# 3xCV.net
KiCad netlist of a schematic drawn in EAGLE
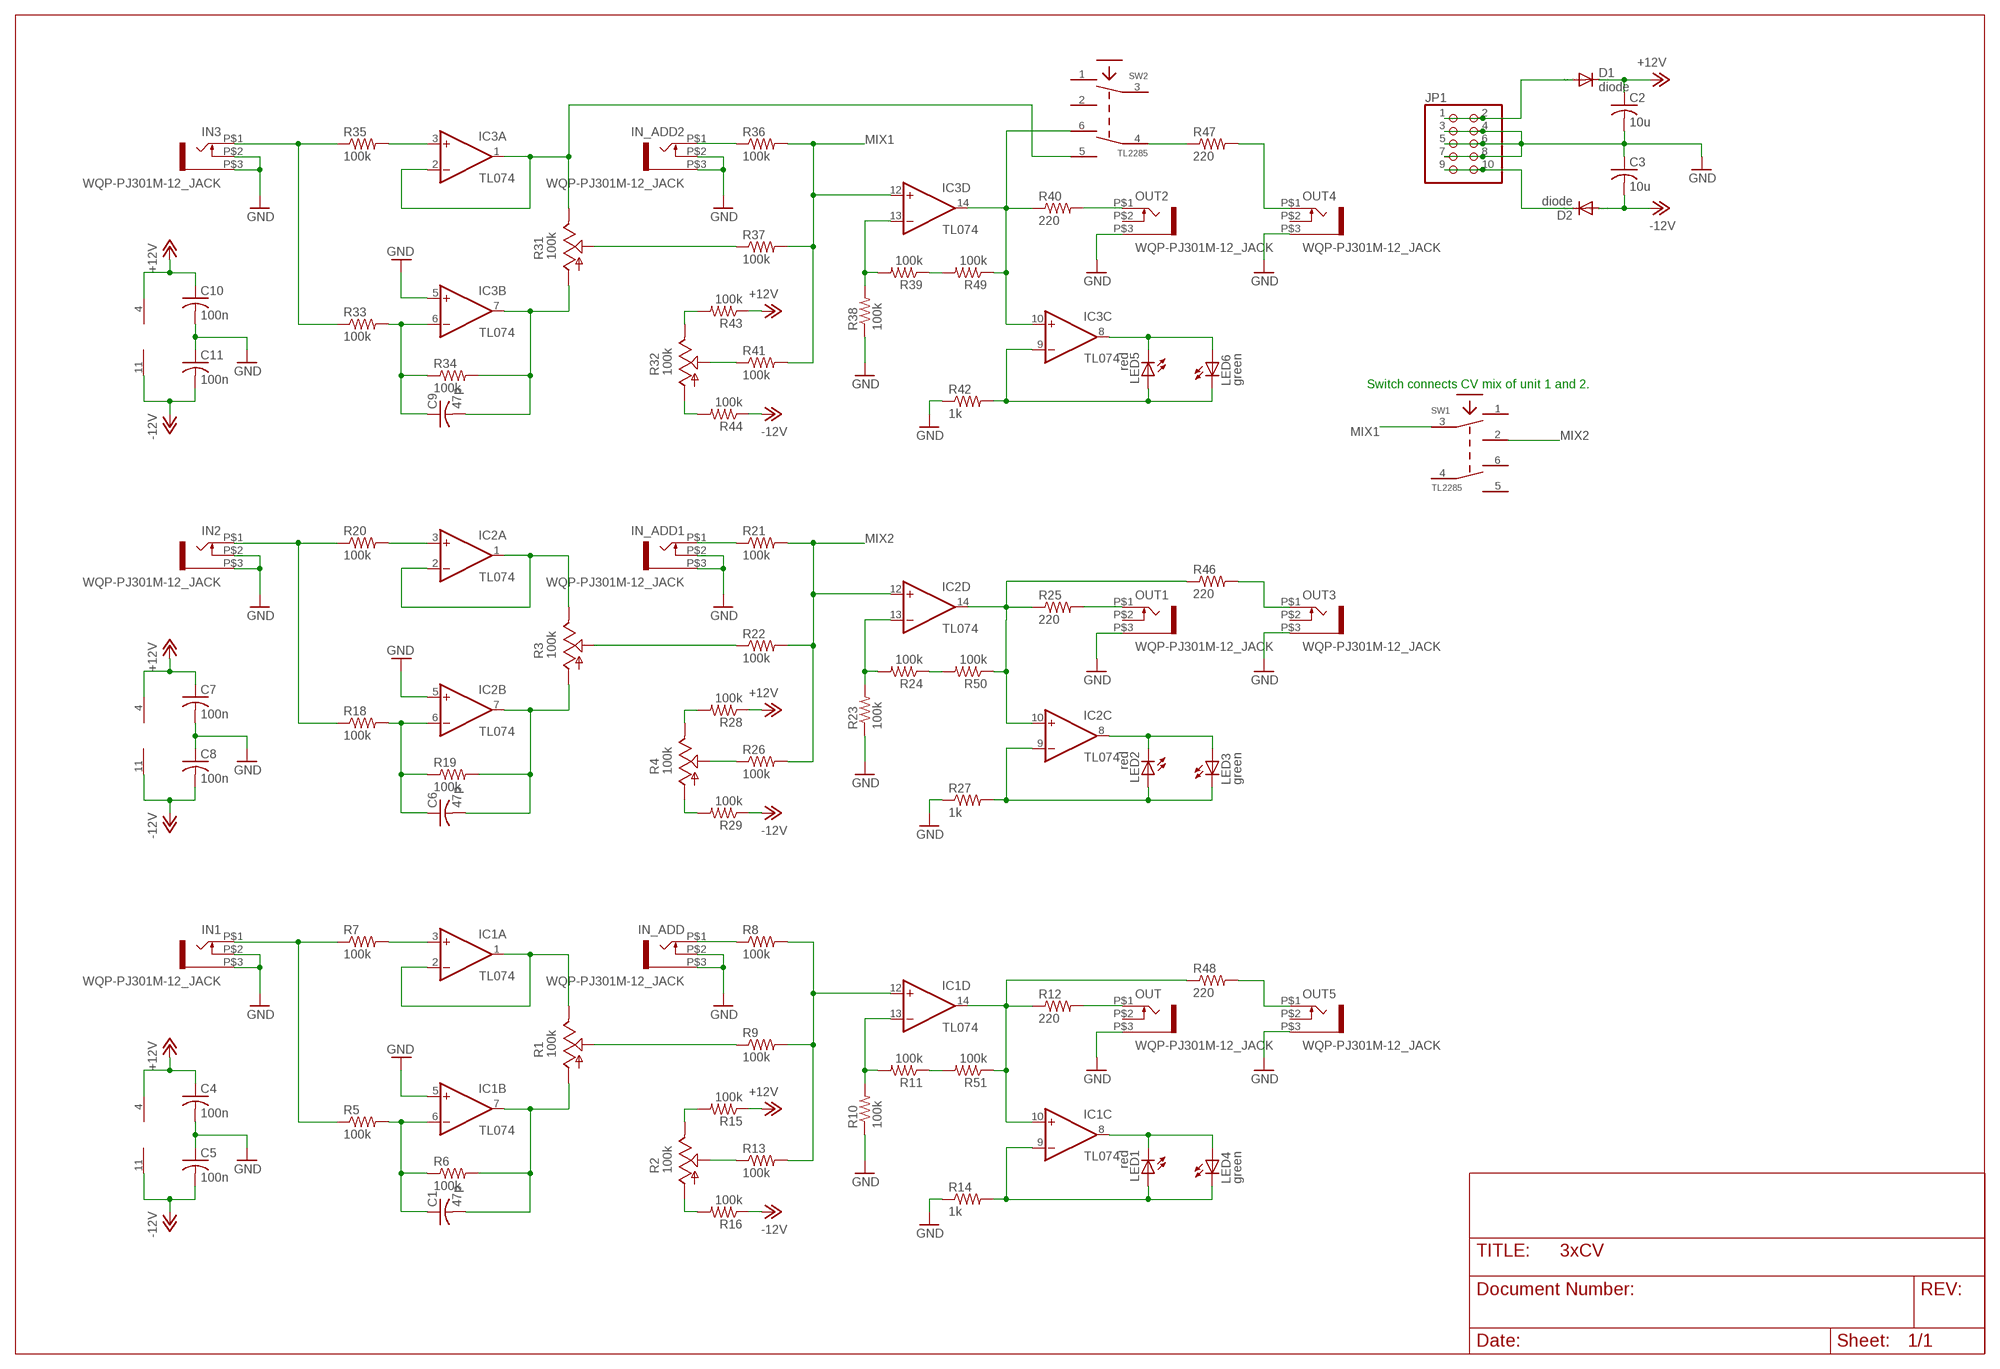
[diagram p0: schematic, sheet 1]

(export (version "E")
  (design (tool "Eeschema 10.0.6"))
  (components
    (comp (ref "C1")
      (value "47p")
      (footprint "eagle-import:C0603")
      (libsource (lib "eagle-import") (part "C-USC0603"))
    )
    (comp (ref "C2")
      (value "10u")
      (footprint "eagle-import:C1206")
      (libsource (lib "eagle-import") (part "C-USC1206"))
    )
    (comp (ref "C3")
      (value "10u")
      (footprint "eagle-import:C1206")
      (libsource (lib "eagle-import") (part "C-USC1206"))
    )
    (comp (ref "C4")
      (value "100n")
      (footprint "eagle-import:C0603")
      (libsource (lib "eagle-import") (part "C-USC0603"))
    )
    (comp (ref "C5")
      (value "100n")
      (footprint "eagle-import:C0603")
      (libsource (lib "eagle-import") (part "C-USC0603"))
    )
    (comp (ref "C6")
      (value "47p")
      (footprint "eagle-import:C0603")
      (libsource (lib "eagle-import") (part "C-USC0603"))
    )
    (comp (ref "C7")
      (value "100n")
      (footprint "eagle-import:C0603")
      (libsource (lib "eagle-import") (part "C-USC0603"))
    )
    (comp (ref "C8")
      (value "100n")
      (footprint "eagle-import:C0603")
      (libsource (lib "eagle-import") (part "C-USC0603"))
    )
    (comp (ref "C9")
      (value "47p")
      (footprint "eagle-import:C0603")
      (libsource (lib "eagle-import") (part "C-USC0603"))
    )
    (comp (ref "C10")
      (value "100n")
      (footprint "eagle-import:C0603")
      (libsource (lib "eagle-import") (part "C-USC0603"))
    )
    (comp (ref "C11")
      (value "100n")
      (footprint "eagle-import:C0603")
      (libsource (lib "eagle-import") (part "C-USC0603"))
    )
    (comp (ref "D1")
      (value "diode")
      (footprint "eagle-import:DO214AA")
      (libsource (lib "eagle-import") (part "DIODE-DO214AA"))
    )
    (comp (ref "D2")
      (value "diode")
      (footprint "eagle-import:DO214AA")
      (libsource (lib "eagle-import") (part "DIODE-DO214AA"))
    )
    (comp (ref "IC1")
      (value "TL074")
      (footprint "eagle-import:SO14")
      (libsource (lib "eagle-import") (part "LM324D"))
    )
    (comp (ref "IC2")
      (value "TL074")
      (footprint "eagle-import:SO14")
      (libsource (lib "eagle-import") (part "LM324D"))
    )
    (comp (ref "IC3")
      (value "TL074")
      (footprint "eagle-import:SO14")
      (libsource (lib "eagle-import") (part "LM324D"))
    )
    (comp (ref "IN1")
      (value "WQP-PJ301M-12_JACK")
      (footprint "eagle-import:WQP-PJ301M-12_JACK")
      (libsource (lib "eagle-import") (part "WQP-PJ301M-12_JACK"))
    )
    (comp (ref "IN2")
      (value "WQP-PJ301M-12_JACK")
      (footprint "eagle-import:WQP-PJ301M-12_JACK")
      (libsource (lib "eagle-import") (part "WQP-PJ301M-12_JACK"))
    )
    (comp (ref "IN3")
      (value "WQP-PJ301M-12_JACK")
      (footprint "eagle-import:WQP-PJ301M-12_JACK")
      (libsource (lib "eagle-import") (part "WQP-PJ301M-12_JACK"))
    )
    (comp (ref "IN_ADD")
      (value "WQP-PJ301M-12_JACK")
      (footprint "eagle-import:WQP-PJ301M-12_JACK")
      (libsource (lib "eagle-import") (part "WQP-PJ301M-12_JACK"))
    )
    (comp (ref "IN_ADD1")
      (value "WQP-PJ301M-12_JACK")
      (footprint "eagle-import:WQP-PJ301M-12_JACK")
      (libsource (lib "eagle-import") (part "WQP-PJ301M-12_JACK"))
    )
    (comp (ref "IN_ADD2")
      (value "WQP-PJ301M-12_JACK")
      (footprint "eagle-import:WQP-PJ301M-12_JACK")
      (libsource (lib "eagle-import") (part "WQP-PJ301M-12_JACK"))
    )
    (comp (ref "JP1")
      (value "PINHD-2X5")
      (footprint "eagle-import:2X05")
      (libsource (lib "eagle-import") (part "PINHD-2X5"))
    )
    (comp (ref "LED1")
      (value "red")
      (footprint "eagle-import:LED3MM")
      (libsource (lib "eagle-import") (part "LED3MM"))
    )
    (comp (ref "LED2")
      (value "red")
      (footprint "eagle-import:LED3MM")
      (libsource (lib "eagle-import") (part "LED3MM"))
    )
    (comp (ref "LED3")
      (value "green")
      (footprint "eagle-import:LED3MM")
      (libsource (lib "eagle-import") (part "LED3MM"))
    )
    (comp (ref "LED4")
      (value "green")
      (footprint "eagle-import:LED3MM")
      (libsource (lib "eagle-import") (part "LED3MM"))
    )
    (comp (ref "LED5")
      (value "red")
      (footprint "eagle-import:LED3MM")
      (libsource (lib "eagle-import") (part "LED3MM"))
    )
    (comp (ref "LED6")
      (value "green")
      (footprint "eagle-import:LED3MM")
      (libsource (lib "eagle-import") (part "LED3MM"))
    )
    (comp (ref "OUT")
      (value "WQP-PJ301M-12_JACK")
      (footprint "eagle-import:WQP-PJ301M-12_JACK")
      (libsource (lib "eagle-import") (part "WQP-PJ301M-12_JACK"))
    )
    (comp (ref "OUT1")
      (value "WQP-PJ301M-12_JACK")
      (footprint "eagle-import:WQP-PJ301M-12_JACK")
      (libsource (lib "eagle-import") (part "WQP-PJ301M-12_JACK"))
    )
    (comp (ref "OUT2")
      (value "WQP-PJ301M-12_JACK")
      (footprint "eagle-import:WQP-PJ301M-12_JACK")
      (libsource (lib "eagle-import") (part "WQP-PJ301M-12_JACK"))
    )
    (comp (ref "OUT3")
      (value "WQP-PJ301M-12_JACK")
      (footprint "eagle-import:WQP-PJ301M-12_JACK")
      (libsource (lib "eagle-import") (part "WQP-PJ301M-12_JACK"))
    )
    (comp (ref "OUT4")
      (value "WQP-PJ301M-12_JACK")
      (footprint "eagle-import:WQP-PJ301M-12_JACK")
      (libsource (lib "eagle-import") (part "WQP-PJ301M-12_JACK"))
    )
    (comp (ref "OUT5")
      (value "WQP-PJ301M-12_JACK")
      (footprint "eagle-import:WQP-PJ301M-12_JACK")
      (libsource (lib "eagle-import") (part "WQP-PJ301M-12_JACK"))
    )
    (comp (ref "R1")
      (value "100k")
      (footprint "eagle-import:ALPS_POT_VERTICAL")
      (libsource (lib "eagle-import") (part "POT_USVERTICAL"))
    )
    (comp (ref "R2")
      (value "100k")
      (footprint "eagle-import:ALPS_POT_VERTICAL")
      (libsource (lib "eagle-import") (part "POT_USVERTICAL"))
    )
    (comp (ref "R3")
      (value "100k")
      (footprint "eagle-import:ALPS_POT_VERTICAL")
      (libsource (lib "eagle-import") (part "POT_USVERTICAL"))
    )
    (comp (ref "R4")
      (value "100k")
      (footprint "eagle-import:ALPS_POT_VERTICAL")
      (libsource (lib "eagle-import") (part "POT_USVERTICAL"))
    )
    (comp (ref "R5")
      (value "100k")
      (footprint "eagle-import:R0603")
      (libsource (lib "eagle-import") (part "R-US_R0603"))
    )
    (comp (ref "R6")
      (value "100k")
      (footprint "eagle-import:R0603")
      (libsource (lib "eagle-import") (part "R-US_R0603"))
    )
    (comp (ref "R7")
      (value "100k")
      (footprint "eagle-import:R0603")
      (libsource (lib "eagle-import") (part "R-US_R0603"))
    )
    (comp (ref "R8")
      (value "100k")
      (footprint "eagle-import:R0603")
      (libsource (lib "eagle-import") (part "R-US_R0603"))
    )
    (comp (ref "R9")
      (value "100k")
      (footprint "eagle-import:R0603")
      (libsource (lib "eagle-import") (part "R-US_R0603"))
    )
    (comp (ref "R10")
      (value "100k")
      (footprint "eagle-import:R0603")
      (libsource (lib "eagle-import") (part "R-US_R0603"))
    )
    (comp (ref "R11")
      (value "100k")
      (footprint "eagle-import:R0603")
      (libsource (lib "eagle-import") (part "R-US_R0603"))
    )
    (comp (ref "R12")
      (value "220")
      (footprint "eagle-import:R0603")
      (libsource (lib "eagle-import") (part "R-US_R0603"))
    )
    (comp (ref "R13")
      (value "100k")
      (footprint "eagle-import:R0603")
      (libsource (lib "eagle-import") (part "R-US_R0603"))
    )
    (comp (ref "R14")
      (value "1k")
      (footprint "eagle-import:R0603")
      (libsource (lib "eagle-import") (part "R-US_R0603"))
    )
    (comp (ref "R15")
      (value "100k")
      (footprint "eagle-import:R0603")
      (libsource (lib "eagle-import") (part "R-US_R0603"))
    )
    (comp (ref "R16")
      (value "100k")
      (footprint "eagle-import:R0603")
      (libsource (lib "eagle-import") (part "R-US_R0603"))
    )
    (comp (ref "R18")
      (value "100k")
      (footprint "eagle-import:R0603")
      (libsource (lib "eagle-import") (part "R-US_R0603"))
    )
    (comp (ref "R19")
      (value "100k")
      (footprint "eagle-import:R0603")
      (libsource (lib "eagle-import") (part "R-US_R0603"))
    )
    (comp (ref "R20")
      (value "100k")
      (footprint "eagle-import:R0603")
      (libsource (lib "eagle-import") (part "R-US_R0603"))
    )
    (comp (ref "R21")
      (value "100k")
      (footprint "eagle-import:R0603")
      (libsource (lib "eagle-import") (part "R-US_R0603"))
    )
    (comp (ref "R22")
      (value "100k")
      (footprint "eagle-import:R0603")
      (libsource (lib "eagle-import") (part "R-US_R0603"))
    )
    (comp (ref "R23")
      (value "100k")
      (footprint "eagle-import:R0603")
      (libsource (lib "eagle-import") (part "R-US_R0603"))
    )
    (comp (ref "R24")
      (value "100k")
      (footprint "eagle-import:R0603")
      (libsource (lib "eagle-import") (part "R-US_R0603"))
    )
    (comp (ref "R25")
      (value "220")
      (footprint "eagle-import:R0603")
      (libsource (lib "eagle-import") (part "R-US_R0603"))
    )
    (comp (ref "R26")
      (value "100k")
      (footprint "eagle-import:R0603")
      (libsource (lib "eagle-import") (part "R-US_R0603"))
    )
    (comp (ref "R27")
      (value "1k")
      (footprint "eagle-import:R0603")
      (libsource (lib "eagle-import") (part "R-US_R0603"))
    )
    (comp (ref "R28")
      (value "100k")
      (footprint "eagle-import:R0603")
      (libsource (lib "eagle-import") (part "R-US_R0603"))
    )
    (comp (ref "R29")
      (value "100k")
      (footprint "eagle-import:R0603")
      (libsource (lib "eagle-import") (part "R-US_R0603"))
    )
    (comp (ref "R31")
      (value "100k")
      (footprint "eagle-import:ALPS_POT_VERTICAL")
      (libsource (lib "eagle-import") (part "POT_USVERTICAL"))
    )
    (comp (ref "R32")
      (value "100k")
      (footprint "eagle-import:ALPS_POT_VERTICAL")
      (libsource (lib "eagle-import") (part "POT_USVERTICAL"))
    )
    (comp (ref "R33")
      (value "100k")
      (footprint "eagle-import:R0603")
      (libsource (lib "eagle-import") (part "R-US_R0603"))
    )
    (comp (ref "R34")
      (value "100k")
      (footprint "eagle-import:R0603")
      (libsource (lib "eagle-import") (part "R-US_R0603"))
    )
    (comp (ref "R35")
      (value "100k")
      (footprint "eagle-import:R0603")
      (libsource (lib "eagle-import") (part "R-US_R0603"))
    )
    (comp (ref "R36")
      (value "100k")
      (footprint "eagle-import:R0603")
      (libsource (lib "eagle-import") (part "R-US_R0603"))
    )
    (comp (ref "R37")
      (value "100k")
      (footprint "eagle-import:R0603")
      (libsource (lib "eagle-import") (part "R-US_R0603"))
    )
    (comp (ref "R38")
      (value "100k")
      (footprint "eagle-import:R0603")
      (libsource (lib "eagle-import") (part "R-US_R0603"))
    )
    (comp (ref "R39")
      (value "100k")
      (footprint "eagle-import:R0603")
      (libsource (lib "eagle-import") (part "R-US_R0603"))
    )
    (comp (ref "R40")
      (value "220")
      (footprint "eagle-import:R0603")
      (libsource (lib "eagle-import") (part "R-US_R0603"))
    )
    (comp (ref "R41")
      (value "100k")
      (footprint "eagle-import:R0603")
      (libsource (lib "eagle-import") (part "R-US_R0603"))
    )
    (comp (ref "R42")
      (value "1k")
      (footprint "eagle-import:R0603")
      (libsource (lib "eagle-import") (part "R-US_R0603"))
    )
    (comp (ref "R43")
      (value "100k")
      (footprint "eagle-import:R0603")
      (libsource (lib "eagle-import") (part "R-US_R0603"))
    )
    (comp (ref "R44")
      (value "100k")
      (footprint "eagle-import:R0603")
      (libsource (lib "eagle-import") (part "R-US_R0603"))
    )
    (comp (ref "R46")
      (value "220")
      (footprint "eagle-import:R0603")
      (libsource (lib "eagle-import") (part "R-US_R0603"))
    )
    (comp (ref "R47")
      (value "220")
      (footprint "eagle-import:R0603")
      (libsource (lib "eagle-import") (part "R-US_R0603"))
    )
    (comp (ref "R48")
      (value "220")
      (footprint "eagle-import:R0603")
      (libsource (lib "eagle-import") (part "R-US_R0603"))
    )
    (comp (ref "R49")
      (value "100k")
      (footprint "eagle-import:R0603")
      (libsource (lib "eagle-import") (part "R-US_R0603"))
    )
    (comp (ref "R50")
      (value "100k")
      (footprint "eagle-import:R0603")
      (libsource (lib "eagle-import") (part "R-US_R0603"))
    )
    (comp (ref "R51")
      (value "100k")
      (footprint "eagle-import:R0603")
      (libsource (lib "eagle-import") (part "R-US_R0603"))
    )
    (comp (ref "SW1")
      (value "TL2285")
      (footprint "eagle-import:TL2285_PCB")
      (libsource (lib "eagle-import") (part "TL2285"))
    )
    (comp (ref "SW2")
      (value "TL2285")
      (footprint "eagle-import:TL2285_PCB")
      (libsource (lib "eagle-import") (part "TL2285"))
    )
  )
  (nets
    (net (code "1") (name "+12V") (class "Default")
      (node (ref "C10") (pin "1") (pinfunction "1_1") (pintype "passive"))
      (node (ref "C2") (pin "1") (pinfunction "1_1") (pintype "passive"))
      (node (ref "C4") (pin "1") (pinfunction "1_1") (pintype "passive"))
      (node (ref "C7") (pin "1") (pinfunction "1_1") (pintype "passive"))
      (node (ref "D1") (pin "C") (pinfunction "C_C") (pintype "passive"))
      (node (ref "IC1") (pin "4") (pinfunction "V+_4") (pintype "power_in"))
      (node (ref "IC2") (pin "4") (pinfunction "V+_4") (pintype "power_in"))
      (node (ref "IC3") (pin "4") (pinfunction "V+_4") (pintype "power_in"))
      (node (ref "R15") (pin "1") (pinfunction "1_1") (pintype "passive"))
      (node (ref "R28") (pin "1") (pinfunction "1_1") (pintype "passive"))
      (node (ref "R43") (pin "1") (pinfunction "1_1") (pintype "passive"))
    )
    (net (code "2") (name "-12V") (class "Default")
      (node (ref "C11") (pin "2") (pinfunction "2_2") (pintype "passive"))
      (node (ref "C3") (pin "2") (pinfunction "2_2") (pintype "passive"))
      (node (ref "C5") (pin "2") (pinfunction "2_2") (pintype "passive"))
      (node (ref "C8") (pin "2") (pinfunction "2_2") (pintype "passive"))
      (node (ref "D2") (pin "A") (pinfunction "A_A") (pintype "passive"))
      (node (ref "IC1") (pin "11") (pinfunction "V-_11") (pintype "power_in"))
      (node (ref "IC2") (pin "11") (pinfunction "V-_11") (pintype "power_in"))
      (node (ref "IC3") (pin "11") (pinfunction "V-_11") (pintype "power_in"))
      (node (ref "R16") (pin "1") (pinfunction "1_1") (pintype "passive"))
      (node (ref "R29") (pin "1") (pinfunction "1_1") (pintype "passive"))
      (node (ref "R44") (pin "1") (pinfunction "1_1") (pintype "passive"))
    )
    (net (code "3") (name "/MIX1") (class "Default")
      (node (ref "IC3") (pin "12") (pinfunction "+IN_12") (pintype "input"))
      (node (ref "R36") (pin "2") (pinfunction "2_2") (pintype "passive"))
      (node (ref "R37") (pin "2") (pinfunction "2_2") (pintype "passive"))
      (node (ref "R41") (pin "2") (pinfunction "2_2") (pintype "passive"))
      (node (ref "SW1") (pin "3") (pinfunction "P3_3") (pintype "bidirectional"))
    )
    (net (code "4") (name "/MIX2") (class "Default")
      (node (ref "IC2") (pin "12") (pinfunction "+IN_12") (pintype "input"))
      (node (ref "R21") (pin "2") (pinfunction "2_2") (pintype "passive"))
      (node (ref "R22") (pin "2") (pinfunction "2_2") (pintype "passive"))
      (node (ref "R26") (pin "2") (pinfunction "2_2") (pintype "passive"))
      (node (ref "SW1") (pin "2") (pinfunction "P2_2") (pintype "bidirectional"))
    )
    (net (code "5") (name "GND") (class "Default")
      (node (ref "C10") (pin "2") (pinfunction "2_2") (pintype "passive"))
      (node (ref "C11") (pin "1") (pinfunction "1_1") (pintype "passive"))
      (node (ref "C2") (pin "2") (pinfunction "2_2") (pintype "passive"))
      (node (ref "C3") (pin "1") (pinfunction "1_1") (pintype "passive"))
      (node (ref "C4") (pin "2") (pinfunction "2_2") (pintype "passive"))
      (node (ref "C5") (pin "1") (pinfunction "1_1") (pintype "passive"))
      (node (ref "C7") (pin "2") (pinfunction "2_2") (pintype "passive"))
      (node (ref "C8") (pin "1") (pinfunction "1_1") (pintype "passive"))
      (node (ref "IC1") (pin "5") (pinfunction "+IN_5") (pintype "input"))
      (node (ref "IC2") (pin "5") (pinfunction "+IN_5") (pintype "input"))
      (node (ref "IC3") (pin "5") (pinfunction "+IN_5") (pintype "input"))
      (node (ref "IN1") (pin "P$2") (pinfunction "3_P$2") (pintype "passive"))
      (node (ref "IN1") (pin "P$3") (pinfunction "1_P$3") (pintype "passive"))
      (node (ref "IN2") (pin "P$2") (pinfunction "3_P$2") (pintype "passive"))
      (node (ref "IN2") (pin "P$3") (pinfunction "1_P$3") (pintype "passive"))
      (node (ref "IN3") (pin "P$2") (pinfunction "3_P$2") (pintype "passive"))
      (node (ref "IN3") (pin "P$3") (pinfunction "1_P$3") (pintype "passive"))
      (node (ref "IN_ADD") (pin "P$2") (pinfunction "3_P$2") (pintype "passive"))
      (node (ref "IN_ADD") (pin "P$3") (pinfunction "1_P$3") (pintype "passive"))
      (node (ref "IN_ADD1") (pin "P$2") (pinfunction "3_P$2") (pintype "passive"))
      (node (ref "IN_ADD1") (pin "P$3") (pinfunction "1_P$3") (pintype "passive"))
      (node (ref "IN_ADD2") (pin "P$2") (pinfunction "3_P$2") (pintype "passive"))
      (node (ref "IN_ADD2") (pin "P$3") (pinfunction "1_P$3") (pintype "passive"))
      (node (ref "JP1") (pin "3") (pinfunction "3_3") (pintype "passive"))
      (node (ref "JP1") (pin "4") (pinfunction "4_4") (pintype "passive"))
      (node (ref "JP1") (pin "5") (pinfunction "5_5") (pintype "passive"))
      (node (ref "JP1") (pin "6") (pinfunction "6_6") (pintype "passive"))
      (node (ref "JP1") (pin "7") (pinfunction "7_7") (pintype "passive"))
      (node (ref "JP1") (pin "8") (pinfunction "8_8") (pintype "passive"))
      (node (ref "OUT") (pin "P$3") (pinfunction "1_P$3") (pintype "passive"))
      (node (ref "OUT1") (pin "P$3") (pinfunction "1_P$3") (pintype "passive"))
      (node (ref "OUT2") (pin "P$3") (pinfunction "1_P$3") (pintype "passive"))
      (node (ref "OUT3") (pin "P$3") (pinfunction "1_P$3") (pintype "passive"))
      (node (ref "OUT4") (pin "P$3") (pinfunction "1_P$3") (pintype "passive"))
      (node (ref "OUT5") (pin "P$3") (pinfunction "1_P$3") (pintype "passive"))
      (node (ref "R10") (pin "1") (pinfunction "1_1") (pintype "passive"))
      (node (ref "R14") (pin "1") (pinfunction "1_1") (pintype "passive"))
      (node (ref "R23") (pin "1") (pinfunction "1_1") (pintype "passive"))
      (node (ref "R27") (pin "1") (pinfunction "1_1") (pintype "passive"))
      (node (ref "R38") (pin "1") (pinfunction "1_1") (pintype "passive"))
      (node (ref "R42") (pin "1") (pinfunction "1_1") (pintype "passive"))
    )
    (net (code "6") (name "Net-(D1-PadA)") (class "Default")
      (node (ref "D1") (pin "A") (pinfunction "A_A") (pintype "passive"))
      (node (ref "JP1") (pin "1") (pinfunction "1_1") (pintype "passive"))
      (node (ref "JP1") (pin "2") (pinfunction "2_2") (pintype "passive"))
    )
    (net (code "7") (name "Net-(D2-PadC)") (class "Default")
      (node (ref "D2") (pin "C") (pinfunction "C_C") (pintype "passive"))
      (node (ref "JP1") (pin "10") (pinfunction "10_10") (pintype "passive"))
      (node (ref "JP1") (pin "9") (pinfunction "9_9") (pintype "passive"))
    )
    (net (code "8") (name "Net-(IC1A-+IN)") (class "Default")
      (node (ref "IC1") (pin "3") (pinfunction "+IN_3") (pintype "input"))
      (node (ref "R7") (pin "2") (pinfunction "2_2") (pintype "passive"))
    )
    (net (code "9") (name "Net-(IC1A--IN)") (class "Default")
      (node (ref "IC1") (pin "1") (pinfunction "OUT_1") (pintype "output"))
      (node (ref "IC1") (pin "2") (pinfunction "-IN_2") (pintype "input"))
      (node (ref "R1") (pin "P$1") (pinfunction "E_P$1") (pintype "passive"))
    )
    (net (code "10") (name "Net-(IC1B--IN)") (class "Default")
      (node (ref "C1") (pin "1") (pinfunction "1_1") (pintype "passive"))
      (node (ref "IC1") (pin "6") (pinfunction "-IN_6") (pintype "input"))
      (node (ref "R5") (pin "2") (pinfunction "2_2") (pintype "passive"))
      (node (ref "R6") (pin "1") (pinfunction "1_1") (pintype "passive"))
    )
    (net (code "11") (name "Net-(IC1B-OUT)") (class "Default")
      (node (ref "C1") (pin "2") (pinfunction "2_2") (pintype "passive"))
      (node (ref "IC1") (pin "7") (pinfunction "OUT_7") (pintype "output"))
      (node (ref "R1") (pin "P$3") (pinfunction "A_P$3") (pintype "passive"))
      (node (ref "R6") (pin "2") (pinfunction "2_2") (pintype "passive"))
    )
    (net (code "12") (name "Net-(IC1C-+IN)") (class "Default")
      (node (ref "IC1") (pin "10") (pinfunction "+IN_10") (pintype "input"))
      (node (ref "IC1") (pin "14") (pinfunction "OUT_14") (pintype "output"))
      (node (ref "R12") (pin "1") (pinfunction "1_1") (pintype "passive"))
      (node (ref "R48") (pin "1") (pinfunction "1_1") (pintype "passive"))
      (node (ref "R51") (pin "1") (pinfunction "1_1") (pintype "passive"))
    )
    (net (code "13") (name "Net-(IC1C--IN)") (class "Default")
      (node (ref "IC1") (pin "9") (pinfunction "-IN_9") (pintype "input"))
      (node (ref "LED1") (pin "A") (pinfunction "A_A") (pintype "passive"))
      (node (ref "LED4") (pin "K") (pinfunction "C_K") (pintype "passive"))
      (node (ref "R14") (pin "2") (pinfunction "2_2") (pintype "passive"))
    )
    (net (code "14") (name "Net-(IC1C-OUT)") (class "Default")
      (node (ref "IC1") (pin "8") (pinfunction "OUT_8") (pintype "output"))
      (node (ref "LED1") (pin "K") (pinfunction "C_K") (pintype "passive"))
      (node (ref "LED4") (pin "A") (pinfunction "A_A") (pintype "passive"))
    )
    (net (code "15") (name "Net-(IC1D-+IN)") (class "Default")
      (node (ref "IC1") (pin "12") (pinfunction "+IN_12") (pintype "input"))
      (node (ref "R13") (pin "2") (pinfunction "2_2") (pintype "passive"))
      (node (ref "R8") (pin "2") (pinfunction "2_2") (pintype "passive"))
      (node (ref "R9") (pin "2") (pinfunction "2_2") (pintype "passive"))
    )
    (net (code "16") (name "Net-(IC1D--IN)") (class "Default")
      (node (ref "IC1") (pin "13") (pinfunction "-IN_13") (pintype "input"))
      (node (ref "R10") (pin "2") (pinfunction "2_2") (pintype "passive"))
      (node (ref "R11") (pin "2") (pinfunction "2_2") (pintype "passive"))
    )
    (net (code "17") (name "Net-(IC2A-+IN)") (class "Default")
      (node (ref "IC2") (pin "3") (pinfunction "+IN_3") (pintype "input"))
      (node (ref "R20") (pin "2") (pinfunction "2_2") (pintype "passive"))
    )
    (net (code "18") (name "Net-(IC2A--IN)") (class "Default")
      (node (ref "IC2") (pin "1") (pinfunction "OUT_1") (pintype "output"))
      (node (ref "IC2") (pin "2") (pinfunction "-IN_2") (pintype "input"))
      (node (ref "R3") (pin "P$1") (pinfunction "E_P$1") (pintype "passive"))
    )
    (net (code "19") (name "Net-(IC2B--IN)") (class "Default")
      (node (ref "C6") (pin "1") (pinfunction "1_1") (pintype "passive"))
      (node (ref "IC2") (pin "6") (pinfunction "-IN_6") (pintype "input"))
      (node (ref "R18") (pin "2") (pinfunction "2_2") (pintype "passive"))
      (node (ref "R19") (pin "1") (pinfunction "1_1") (pintype "passive"))
    )
    (net (code "20") (name "Net-(IC2B-OUT)") (class "Default")
      (node (ref "C6") (pin "2") (pinfunction "2_2") (pintype "passive"))
      (node (ref "IC2") (pin "7") (pinfunction "OUT_7") (pintype "output"))
      (node (ref "R19") (pin "2") (pinfunction "2_2") (pintype "passive"))
      (node (ref "R3") (pin "P$3") (pinfunction "A_P$3") (pintype "passive"))
    )
    (net (code "21") (name "Net-(IC2C-+IN)") (class "Default")
      (node (ref "IC2") (pin "10") (pinfunction "+IN_10") (pintype "input"))
      (node (ref "IC2") (pin "14") (pinfunction "OUT_14") (pintype "output"))
      (node (ref "R25") (pin "1") (pinfunction "1_1") (pintype "passive"))
      (node (ref "R46") (pin "1") (pinfunction "1_1") (pintype "passive"))
      (node (ref "R50") (pin "1") (pinfunction "1_1") (pintype "passive"))
    )
    (net (code "22") (name "Net-(IC2C--IN)") (class "Default")
      (node (ref "IC2") (pin "9") (pinfunction "-IN_9") (pintype "input"))
      (node (ref "LED2") (pin "A") (pinfunction "A_A") (pintype "passive"))
      (node (ref "LED3") (pin "K") (pinfunction "C_K") (pintype "passive"))
      (node (ref "R27") (pin "2") (pinfunction "2_2") (pintype "passive"))
    )
    (net (code "23") (name "Net-(IC2C-OUT)") (class "Default")
      (node (ref "IC2") (pin "8") (pinfunction "OUT_8") (pintype "output"))
      (node (ref "LED2") (pin "K") (pinfunction "C_K") (pintype "passive"))
      (node (ref "LED3") (pin "A") (pinfunction "A_A") (pintype "passive"))
    )
    (net (code "24") (name "Net-(IC2D--IN)") (class "Default")
      (node (ref "IC2") (pin "13") (pinfunction "-IN_13") (pintype "input"))
      (node (ref "R23") (pin "2") (pinfunction "2_2") (pintype "passive"))
      (node (ref "R24") (pin "2") (pinfunction "2_2") (pintype "passive"))
    )
    (net (code "25") (name "Net-(IC3A-+IN)") (class "Default")
      (node (ref "IC3") (pin "3") (pinfunction "+IN_3") (pintype "input"))
      (node (ref "R35") (pin "2") (pinfunction "2_2") (pintype "passive"))
    )
    (net (code "26") (name "Net-(IC3A--IN)") (class "Default")
      (node (ref "IC3") (pin "1") (pinfunction "OUT_1") (pintype "output"))
      (node (ref "IC3") (pin "2") (pinfunction "-IN_2") (pintype "input"))
      (node (ref "R31") (pin "P$1") (pinfunction "E_P$1") (pintype "passive"))
      (node (ref "SW2") (pin "5") (pinfunction "P5_5") (pintype "bidirectional"))
    )
    (net (code "27") (name "Net-(IC3B--IN)") (class "Default")
      (node (ref "C9") (pin "1") (pinfunction "1_1") (pintype "passive"))
      (node (ref "IC3") (pin "6") (pinfunction "-IN_6") (pintype "input"))
      (node (ref "R33") (pin "2") (pinfunction "2_2") (pintype "passive"))
      (node (ref "R34") (pin "1") (pinfunction "1_1") (pintype "passive"))
    )
    (net (code "28") (name "Net-(IC3B-OUT)") (class "Default")
      (node (ref "C9") (pin "2") (pinfunction "2_2") (pintype "passive"))
      (node (ref "IC3") (pin "7") (pinfunction "OUT_7") (pintype "output"))
      (node (ref "R31") (pin "P$3") (pinfunction "A_P$3") (pintype "passive"))
      (node (ref "R34") (pin "2") (pinfunction "2_2") (pintype "passive"))
    )
    (net (code "29") (name "Net-(IC3C-+IN)") (class "Default")
      (node (ref "IC3") (pin "10") (pinfunction "+IN_10") (pintype "input"))
      (node (ref "IC3") (pin "14") (pinfunction "OUT_14") (pintype "output"))
      (node (ref "R40") (pin "1") (pinfunction "1_1") (pintype "passive"))
      (node (ref "R49") (pin "1") (pinfunction "1_1") (pintype "passive"))
      (node (ref "SW2") (pin "6") (pinfunction "P6_6") (pintype "bidirectional"))
    )
    (net (code "30") (name "Net-(IC3C--IN)") (class "Default")
      (node (ref "IC3") (pin "9") (pinfunction "-IN_9") (pintype "input"))
      (node (ref "LED5") (pin "A") (pinfunction "A_A") (pintype "passive"))
      (node (ref "LED6") (pin "K") (pinfunction "C_K") (pintype "passive"))
      (node (ref "R42") (pin "2") (pinfunction "2_2") (pintype "passive"))
    )
    (net (code "31") (name "Net-(IC3C-OUT)") (class "Default")
      (node (ref "IC3") (pin "8") (pinfunction "OUT_8") (pintype "output"))
      (node (ref "LED5") (pin "K") (pinfunction "C_K") (pintype "passive"))
      (node (ref "LED6") (pin "A") (pinfunction "A_A") (pintype "passive"))
    )
    (net (code "32") (name "Net-(IC3D--IN)") (class "Default")
      (node (ref "IC3") (pin "13") (pinfunction "-IN_13") (pintype "input"))
      (node (ref "R38") (pin "2") (pinfunction "2_2") (pintype "passive"))
      (node (ref "R39") (pin "2") (pinfunction "2_2") (pintype "passive"))
    )
    (net (code "33") (name "Net-(IN1-2)") (class "Default")
      (node (ref "IN1") (pin "P$1") (pinfunction "2_P$1") (pintype "passive"))
      (node (ref "R5") (pin "1") (pinfunction "1_1") (pintype "passive"))
      (node (ref "R7") (pin "1") (pinfunction "1_1") (pintype "passive"))
    )
    (net (code "34") (name "Net-(IN2-2)") (class "Default")
      (node (ref "IN2") (pin "P$1") (pinfunction "2_P$1") (pintype "passive"))
      (node (ref "R18") (pin "1") (pinfunction "1_1") (pintype "passive"))
      (node (ref "R20") (pin "1") (pinfunction "1_1") (pintype "passive"))
    )
    (net (code "35") (name "Net-(IN3-2)") (class "Default")
      (node (ref "IN3") (pin "P$1") (pinfunction "2_P$1") (pintype "passive"))
      (node (ref "R33") (pin "1") (pinfunction "1_1") (pintype "passive"))
      (node (ref "R35") (pin "1") (pinfunction "1_1") (pintype "passive"))
    )
    (net (code "36") (name "Net-(IN_ADD-2)") (class "Default")
      (node (ref "IN_ADD") (pin "P$1") (pinfunction "2_P$1") (pintype "passive"))
      (node (ref "R8") (pin "1") (pinfunction "1_1") (pintype "passive"))
    )
    (net (code "37") (name "Net-(IN_ADD1-2)") (class "Default")
      (node (ref "IN_ADD1") (pin "P$1") (pinfunction "2_P$1") (pintype "passive"))
      (node (ref "R21") (pin "1") (pinfunction "1_1") (pintype "passive"))
    )
    (net (code "38") (name "Net-(IN_ADD2-2)") (class "Default")
      (node (ref "IN_ADD2") (pin "P$1") (pinfunction "2_P$1") (pintype "passive"))
      (node (ref "R36") (pin "1") (pinfunction "1_1") (pintype "passive"))
    )
    (net (code "39") (name "Net-(OUT-2)") (class "Default")
      (node (ref "OUT") (pin "P$1") (pinfunction "2_P$1") (pintype "passive"))
      (node (ref "R12") (pin "2") (pinfunction "2_2") (pintype "passive"))
    )
    (net (code "40") (name "Net-(OUT1-2)") (class "Default")
      (node (ref "OUT1") (pin "P$1") (pinfunction "2_P$1") (pintype "passive"))
      (node (ref "R25") (pin "2") (pinfunction "2_2") (pintype "passive"))
    )
    (net (code "41") (name "Net-(OUT2-2)") (class "Default")
      (node (ref "OUT2") (pin "P$1") (pinfunction "2_P$1") (pintype "passive"))
      (node (ref "R40") (pin "2") (pinfunction "2_2") (pintype "passive"))
    )
    (net (code "42") (name "Net-(OUT3-2)") (class "Default")
      (node (ref "OUT3") (pin "P$1") (pinfunction "2_P$1") (pintype "passive"))
      (node (ref "R46") (pin "2") (pinfunction "2_2") (pintype "passive"))
    )
    (net (code "43") (name "Net-(OUT4-2)") (class "Default")
      (node (ref "OUT4") (pin "P$1") (pinfunction "2_P$1") (pintype "passive"))
      (node (ref "R47") (pin "2") (pinfunction "2_2") (pintype "passive"))
    )
    (net (code "44") (name "Net-(OUT5-2)") (class "Default")
      (node (ref "OUT5") (pin "P$1") (pinfunction "2_P$1") (pintype "passive"))
      (node (ref "R48") (pin "2") (pinfunction "2_2") (pintype "passive"))
    )
    (net (code "45") (name "Net-(R1-S)") (class "Default")
      (node (ref "R1") (pin "P$2") (pinfunction "S_P$2") (pintype "passive"))
      (node (ref "R9") (pin "1") (pinfunction "1_1") (pintype "passive"))
    )
    (net (code "46") (name "Net-(R2-A)") (class "Default")
      (node (ref "R16") (pin "2") (pinfunction "2_2") (pintype "passive"))
      (node (ref "R2") (pin "P$3") (pinfunction "A_P$3") (pintype "passive"))
    )
    (net (code "47") (name "Net-(R2-E)") (class "Default")
      (node (ref "R15") (pin "2") (pinfunction "2_2") (pintype "passive"))
      (node (ref "R2") (pin "P$1") (pinfunction "E_P$1") (pintype "passive"))
    )
    (net (code "48") (name "Net-(R2-S)") (class "Default")
      (node (ref "R13") (pin "1") (pinfunction "1_1") (pintype "passive"))
      (node (ref "R2") (pin "P$2") (pinfunction "S_P$2") (pintype "passive"))
    )
    (net (code "49") (name "Net-(R3-S)") (class "Default")
      (node (ref "R22") (pin "1") (pinfunction "1_1") (pintype "passive"))
      (node (ref "R3") (pin "P$2") (pinfunction "S_P$2") (pintype "passive"))
    )
    (net (code "50") (name "Net-(R4-A)") (class "Default")
      (node (ref "R29") (pin "2") (pinfunction "2_2") (pintype "passive"))
      (node (ref "R4") (pin "P$3") (pinfunction "A_P$3") (pintype "passive"))
    )
    (net (code "51") (name "Net-(R4-E)") (class "Default")
      (node (ref "R28") (pin "2") (pinfunction "2_2") (pintype "passive"))
      (node (ref "R4") (pin "P$1") (pinfunction "E_P$1") (pintype "passive"))
    )
    (net (code "52") (name "Net-(R4-S)") (class "Default")
      (node (ref "R26") (pin "1") (pinfunction "1_1") (pintype "passive"))
      (node (ref "R4") (pin "P$2") (pinfunction "S_P$2") (pintype "passive"))
    )
    (net (code "53") (name "Net-(R11-Pad1)") (class "Default")
      (node (ref "R11") (pin "1") (pinfunction "1_1") (pintype "passive"))
      (node (ref "R51") (pin "2") (pinfunction "2_2") (pintype "passive"))
    )
    (net (code "54") (name "Net-(R24-Pad1)") (class "Default")
      (node (ref "R24") (pin "1") (pinfunction "1_1") (pintype "passive"))
      (node (ref "R50") (pin "2") (pinfunction "2_2") (pintype "passive"))
    )
    (net (code "55") (name "Net-(R31-S)") (class "Default")
      (node (ref "R31") (pin "P$2") (pinfunction "S_P$2") (pintype "passive"))
      (node (ref "R37") (pin "1") (pinfunction "1_1") (pintype "passive"))
    )
    (net (code "56") (name "Net-(R32-A)") (class "Default")
      (node (ref "R32") (pin "P$3") (pinfunction "A_P$3") (pintype "passive"))
      (node (ref "R44") (pin "2") (pinfunction "2_2") (pintype "passive"))
    )
    (net (code "57") (name "Net-(R32-E)") (class "Default")
      (node (ref "R32") (pin "P$1") (pinfunction "E_P$1") (pintype "passive"))
      (node (ref "R43") (pin "2") (pinfunction "2_2") (pintype "passive"))
    )
    (net (code "58") (name "Net-(R32-S)") (class "Default")
      (node (ref "R32") (pin "P$2") (pinfunction "S_P$2") (pintype "passive"))
      (node (ref "R41") (pin "1") (pinfunction "1_1") (pintype "passive"))
    )
    (net (code "59") (name "Net-(R39-Pad1)") (class "Default")
      (node (ref "R39") (pin "1") (pinfunction "1_1") (pintype "passive"))
      (node (ref "R49") (pin "2") (pinfunction "2_2") (pintype "passive"))
    )
    (net (code "60") (name "Net-(SW2-P4)") (class "Default")
      (node (ref "R47") (pin "1") (pinfunction "1_1") (pintype "passive"))
      (node (ref "SW2") (pin "4") (pinfunction "P4_4") (pintype "bidirectional"))
    )
    (net (code "61") (name "unconnected-(OUT-3-PadP$2)") (class "Default")
      (node (ref "OUT") (pin "P$2") (pinfunction "3_P$2") (pintype "passive"))
    )
    (net (code "62") (name "unconnected-(OUT1-3-PadP$2)") (class "Default")
      (node (ref "OUT1") (pin "P$2") (pinfunction "3_P$2") (pintype "passive"))
    )
    (net (code "63") (name "unconnected-(OUT2-3-PadP$2)") (class "Default")
      (node (ref "OUT2") (pin "P$2") (pinfunction "3_P$2") (pintype "passive"))
    )
    (net (code "64") (name "unconnected-(OUT3-3-PadP$2)") (class "Default")
      (node (ref "OUT3") (pin "P$2") (pinfunction "3_P$2") (pintype "passive"))
    )
    (net (code "65") (name "unconnected-(OUT4-3-PadP$2)") (class "Default")
      (node (ref "OUT4") (pin "P$2") (pinfunction "3_P$2") (pintype "passive"))
    )
    (net (code "66") (name "unconnected-(OUT5-3-PadP$2)") (class "Default")
      (node (ref "OUT5") (pin "P$2") (pinfunction "3_P$2") (pintype "passive"))
    )
    (net (code "67") (name "unconnected-(SW1-P1-Pad1)") (class "Default")
      (node (ref "SW1") (pin "1") (pinfunction "P1_1") (pintype "bidirectional"))
    )
    (net (code "68") (name "unconnected-(SW1-P4-Pad4)") (class "Default")
      (node (ref "SW1") (pin "4") (pinfunction "P4_4") (pintype "bidirectional"))
    )
    (net (code "69") (name "unconnected-(SW1-P5-Pad5)") (class "Default")
      (node (ref "SW1") (pin "5") (pinfunction "P5_5") (pintype "bidirectional"))
    )
    (net (code "70") (name "unconnected-(SW1-P6-Pad6)") (class "Default")
      (node (ref "SW1") (pin "6") (pinfunction "P6_6") (pintype "bidirectional"))
    )
    (net (code "71") (name "unconnected-(SW2-P1-Pad1)") (class "Default")
      (node (ref "SW2") (pin "1") (pinfunction "P1_1") (pintype "bidirectional"))
    )
    (net (code "72") (name "unconnected-(SW2-P2-Pad2)") (class "Default")
      (node (ref "SW2") (pin "2") (pinfunction "P2_2") (pintype "bidirectional"))
    )
    (net (code "73") (name "unconnected-(SW2-P3-Pad3)") (class "Default")
      (node (ref "SW2") (pin "3") (pinfunction "P3_3") (pintype "bidirectional"))
    )
  )
)
